# ad.net
KiCad netlist of a schematic drawn in Altium Designer
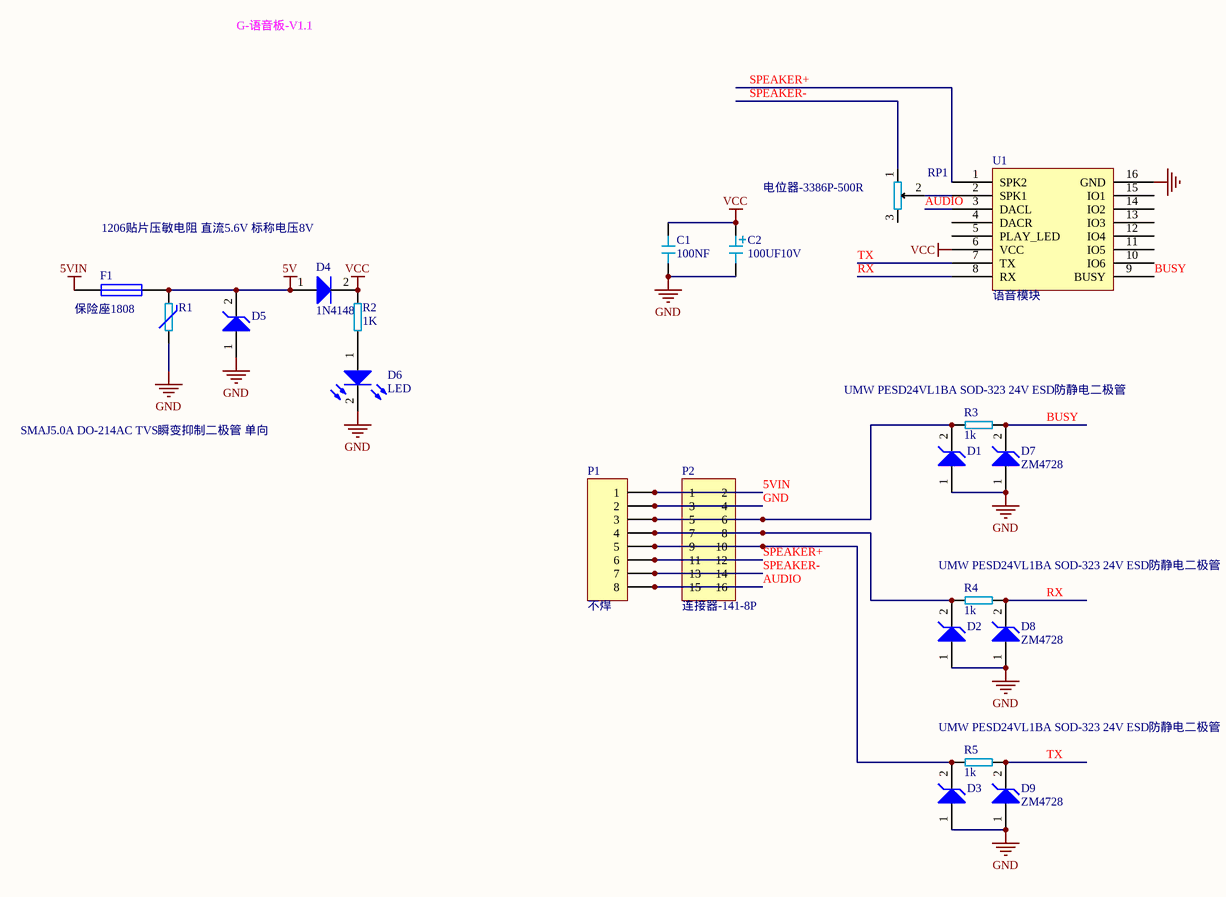
[diagram p0: ad.SchDoc]

(export (version "E")
  (design (tool "Eeschema 10.0.6"))
  (components
    (comp (ref "C1")
      (value "100NF")
      (footprint "C0603")
      (description "贴片电容")
      (libsource (lib "base") (part "C0603"))
    )
    (comp (ref "C2")
      (value "100UF10V")
      (footprint "C3528+")
      (description "铝电解电容")
      (libsource (lib "base") (part "C+"))
    )
    (comp (ref "D1")
      (value "UMW PESD24VL1BA SOD-323 24V ESD防静电二极管")
      (footprint "SOD323")
      (description "TVS")
      (fields (field (name "PUBLISHER") "Altium Limited"))
      (libsource (lib "base") (part "TVS-SMA"))
    )
    (comp (ref "D2")
      (value "UMW PESD24VL1BA SOD-323 24V ESD防静电二极管")
      (footprint "SOD323")
      (description "TVS")
      (fields (field (name "PUBLISHER") "Altium Limited"))
      (libsource (lib "base") (part "TVS-SMA"))
    )
    (comp (ref "D3")
      (value "UMW PESD24VL1BA SOD-323 24V ESD防静电二极管")
      (footprint "SOD323")
      (description "TVS")
      (fields (field (name "PUBLISHER") "Altium Limited"))
      (libsource (lib "base") (part "TVS-SMA"))
    )
    (comp (ref "D4")
      (value "1N4148")
      (footprint "SOD123")
      (description "二极管")
      (fields (field (name "PUBLISHER") "Altium Limited"))
      (libsource (lib "base") (part "DD"))
    )
    (comp (ref "D5")
      (value "SMAJ5.0A DO-214AC TVS瞬变抑制二极管 单向")
      (footprint "SMA")
      (description "TVS")
      (fields (field (name "PUBLISHER") "Altium Limited"))
      (libsource (lib "base") (part "TVS-SMA"))
    )
    (comp (ref "D6")
      (value "LED")
      (footprint "LED0603")
      (description "LED0603")
      (fields (field (name "PUBLISHER") "Altium Limited"))
      (libsource (lib "base") (part "LED0603"))
    )
    (comp (ref "D7")
      (value "ZM4728")
      (footprint "D1206")
      (description "稳压管")
      (fields (field (name "PUBLISHER") "Altium Limited"))
      (libsource (lib "base") (part "TVS-SMA"))
    )
    (comp (ref "D8")
      (value "ZM4728")
      (footprint "D1206")
      (description "稳压管")
      (fields (field (name "PUBLISHER") "Altium Limited"))
      (libsource (lib "base") (part "TVS-SMA"))
    )
    (comp (ref "D9")
      (value "ZM4728")
      (footprint "D1206")
      (description "稳压管")
      (fields (field (name "PUBLISHER") "Altium Limited"))
      (libsource (lib "base") (part "TVS-SMA"))
    )
    (comp (ref "F1")
      (value "保险座1808")
      (footprint "F1808-ZUO")
      (description "自恢复保险")
      (fields (field (name "PUBLISHER") "Altium Limited"))
      (libsource (lib "base") (part "Fuse0805"))
    )
    (comp (ref "P1")
      (value "不焊")
      (footprint "SIP8")
      (description "连接器")
      (fields (field (name "PUBLISHER") "Altium Limited"))
      (libsource (lib "base") (part "SIP8"))
    )
    (comp (ref "P2")
      (value "连接器-141-8P")
      (footprint "141V-8P")
      (description "连接器")
      (fields (field (name "PUBLISHER") "Altium Limited"))
      (libsource (lib "base") (part "DIC16"))
    )
    (comp (ref "R1")
      (value "1206贴片压敏电阻 直流5.6V 标称电压8V")
      (footprint "R1206")
      (description "压敏电阻")
      (libsource (lib "base") (part "RV"))
    )
    (comp (ref "R2")
      (value "1K")
      (footprint "R0603")
      (description "贴片电阻")
      (libsource (lib "base") (part "R-0603"))
    )
    (comp (ref "R3")
      (value "1k")
      (footprint "R0603")
      (description "贴片电阻")
      (libsource (lib "base") (part "R-0603"))
    )
    (comp (ref "R4")
      (value "1k")
      (footprint "R0603")
      (description "贴片电阻")
      (libsource (lib "base") (part "R-0603"))
    )
    (comp (ref "R5")
      (value "1k")
      (footprint "R0603")
      (description "贴片电阻")
      (libsource (lib "base") (part "R-0603"))
    )
    (comp (ref "RP1")
      (value "电位器-3386P-500R")
      (footprint "RR-3386")
      (description "电位器")
      (libsource (lib "base") (part "RR"))
    )
    (comp (ref "U1") (value "语音模块") (footprint "YYMK") (libsource (lib "yuyin") (part "YYMK")))
  )
  (nets
    (net (code "1") (name "/AUDIO") (class "Default")
      (node (ref "P1") (pin "8") (pinfunction "8_8") (pintype "passive"))
      (node (ref "P2") (pin "15") (pinfunction "15_15") (pintype "passive"))
      (node (ref "P2") (pin "16") (pinfunction "16_16") (pintype "passive"))
      (node (ref "U1") (pin "3") (pinfunction "DACL_3") (pintype "passive"))
    )
    (net (code "2") (name "/BUSY") (class "Default")
      (node (ref "D7") (pin "2") (pinfunction "2_2") (pintype "passive"))
      (node (ref "R3") (pin "1") (pinfunction "1_1") (pintype "passive"))
      (node (ref "U1") (pin "9") (pinfunction "BUSY_9") (pintype "passive"))
    )
    (net (code "4") (name "/RX") (class "Default")
      (node (ref "D8") (pin "2") (pinfunction "2_2") (pintype "passive"))
      (node (ref "R4") (pin "1") (pinfunction "1_1") (pintype "passive"))
      (node (ref "U1") (pin "8") (pinfunction "RX_8") (pintype "passive"))
    )
    (net (code "5") (name "/SPEAKER+") (class "Default")
      (node (ref "P1") (pin "6") (pinfunction "6_6") (pintype "passive"))
      (node (ref "P2") (pin "11") (pinfunction "11_11") (pintype "passive"))
      (node (ref "P2") (pin "12") (pinfunction "12_12") (pintype "passive"))
      (node (ref "U1") (pin "1") (pinfunction "SPK2_1") (pintype "passive"))
    )
    (net (code "6") (name "/SPEAKER-") (class "Default")
      (node (ref "P1") (pin "7") (pinfunction "7_7") (pintype "passive"))
      (node (ref "P2") (pin "13") (pinfunction "13_13") (pintype "passive"))
      (node (ref "P2") (pin "14") (pinfunction "14_14") (pintype "passive"))
      (node (ref "RP1") (pin "1") (pinfunction "1_1") (pintype "passive"))
    )
    (net (code "7") (name "/TX") (class "Default")
      (node (ref "D9") (pin "2") (pinfunction "2_2") (pintype "passive"))
      (node (ref "R5") (pin "1") (pinfunction "1_1") (pintype "passive"))
      (node (ref "U1") (pin "7") (pinfunction "TX_7") (pintype "passive"))
    )
    (net (code "8") (name "5V") (class "Default")
      (node (ref "D4") (pin "1") (pinfunction "A_1") (pintype "passive"))
      (node (ref "D5") (pin "2") (pinfunction "2_2") (pintype "passive"))
      (node (ref "F1") (pin "2") (pinfunction "2_2") (pintype "passive"))
      (node (ref "R1") (pin "2") (pinfunction "2_2") (pintype "passive"))
    )
    (net (code "9") (name "5VIN") (class "Default")
      (node (ref "F1") (pin "1") (pinfunction "1_1") (pintype "passive"))
      (node (ref "P1") (pin "1") (pinfunction "1_1") (pintype "passive"))
      (node (ref "P2") (pin "1") (pinfunction "1_1") (pintype "passive"))
      (node (ref "P2") (pin "2") (pinfunction "2_2") (pintype "passive"))
    )
    (net (code "10") (name "GND") (class "Default")
      (node (ref "C1") (pin "1") (pinfunction "1_1") (pintype "passive"))
      (node (ref "C2") (pin "2") (pinfunction "2_2") (pintype "passive"))
      (node (ref "D1") (pin "1") (pinfunction "1_1") (pintype "passive"))
      (node (ref "D2") (pin "1") (pinfunction "1_1") (pintype "passive"))
      (node (ref "D3") (pin "1") (pinfunction "1_1") (pintype "passive"))
      (node (ref "D5") (pin "1") (pinfunction "1_1") (pintype "passive"))
      (node (ref "D6") (pin "2") (pinfunction "K_2") (pintype "passive"))
      (node (ref "D7") (pin "1") (pinfunction "1_1") (pintype "passive"))
      (node (ref "D8") (pin "1") (pinfunction "1_1") (pintype "passive"))
      (node (ref "D9") (pin "1") (pinfunction "1_1") (pintype "passive"))
      (node (ref "P1") (pin "2") (pinfunction "2_2") (pintype "passive"))
      (node (ref "P2") (pin "3") (pinfunction "3_3") (pintype "passive"))
      (node (ref "P2") (pin "4") (pinfunction "4_4") (pintype "passive"))
      (node (ref "R1") (pin "1") (pinfunction "1_1") (pintype "passive"))
      (node (ref "U1") (pin "16") (pinfunction "GND_16") (pintype "passive"))
    )
    (net (code "11") (name "Net-(D1-Pad2)") (class "Default")
      (node (ref "D1") (pin "2") (pinfunction "2_2") (pintype "passive"))
      (node (ref "P1") (pin "3") (pinfunction "3_3") (pintype "passive"))
      (node (ref "P2") (pin "5") (pinfunction "5_5") (pintype "passive"))
      (node (ref "P2") (pin "6") (pinfunction "6_6") (pintype "passive"))
      (node (ref "R3") (pin "2") (pinfunction "2_2") (pintype "passive"))
    )
    (net (code "12") (name "Net-(D2-Pad2)") (class "Default")
      (node (ref "D2") (pin "2") (pinfunction "2_2") (pintype "passive"))
      (node (ref "P1") (pin "4") (pinfunction "4_4") (pintype "passive"))
      (node (ref "P2") (pin "7") (pinfunction "7_7") (pintype "passive"))
      (node (ref "P2") (pin "8") (pinfunction "8_8") (pintype "passive"))
      (node (ref "R4") (pin "2") (pinfunction "2_2") (pintype "passive"))
    )
    (net (code "13") (name "Net-(D3-Pad2)") (class "Default")
      (node (ref "D3") (pin "2") (pinfunction "2_2") (pintype "passive"))
      (node (ref "P1") (pin "5") (pinfunction "5_5") (pintype "passive"))
      (node (ref "P2") (pin "10") (pinfunction "10_10") (pintype "passive"))
      (node (ref "P2") (pin "9") (pinfunction "9_9") (pintype "passive"))
      (node (ref "R5") (pin "2") (pinfunction "2_2") (pintype "passive"))
    )
    (net (code "14") (name "Net-(D6-A)") (class "Default")
      (node (ref "D6") (pin "1") (pinfunction "A_1") (pintype "passive"))
      (node (ref "R2") (pin "1") (pinfunction "1_1") (pintype "passive"))
    )
    (net (code "15") (name "Net-(U1-SPK1)") (class "Default")
      (node (ref "RP1") (pin "2") (pinfunction "2_2") (pintype "passive"))
      (node (ref "U1") (pin "2") (pinfunction "SPK1_2") (pintype "passive"))
    )
    (net (code "16") (name "VCC") (class "Default")
      (node (ref "C1") (pin "2") (pinfunction "2_2") (pintype "passive"))
      (node (ref "C2") (pin "1") (pinfunction "1_1") (pintype "passive"))
      (node (ref "D4") (pin "2") (pinfunction "K_2") (pintype "passive"))
      (node (ref "R2") (pin "2") (pinfunction "2_2") (pintype "passive"))
      (node (ref "U1") (pin "6") (pinfunction "VCC_6") (pintype "passive"))
    )
    (net (code "17") (name "unconnected-(RP1-Pad3)") (class "Default")
      (node (ref "RP1") (pin "3") (pinfunction "3_3") (pintype "passive"))
    )
    (net (code "18") (name "unconnected-(U1-DACR-Pad4)") (class "Default")
      (node (ref "U1") (pin "4") (pinfunction "DACR_4") (pintype "passive"))
    )
    (net (code "19") (name "unconnected-(U1-IO1-Pad15)") (class "Default")
      (node (ref "U1") (pin "15") (pinfunction "IO1_15") (pintype "passive"))
    )
    (net (code "20") (name "unconnected-(U1-IO2-Pad14)") (class "Default")
      (node (ref "U1") (pin "14") (pinfunction "IO2_14") (pintype "passive"))
    )
    (net (code "21") (name "unconnected-(U1-IO3-Pad13)") (class "Default")
      (node (ref "U1") (pin "13") (pinfunction "IO3_13") (pintype "passive"))
    )
    (net (code "22") (name "unconnected-(U1-IO4-Pad12)") (class "Default")
      (node (ref "U1") (pin "12") (pinfunction "IO4_12") (pintype "passive"))
    )
    (net (code "23") (name "unconnected-(U1-IO5-Pad11)") (class "Default")
      (node (ref "U1") (pin "11") (pinfunction "IO5_11") (pintype "passive"))
    )
    (net (code "24") (name "unconnected-(U1-IO6-Pad10)") (class "Default")
      (node (ref "U1") (pin "10") (pinfunction "IO6_10") (pintype "passive"))
    )
    (net (code "25") (name "unconnected-(U1-PLAY_LED-Pad5)") (class "Default")
      (node (ref "U1") (pin "5") (pinfunction "PLAY_LED_5") (pintype "passive"))
    )
  )
)
